# Sch.net
KiCad netlist of a schematic drawn in Altium Designer
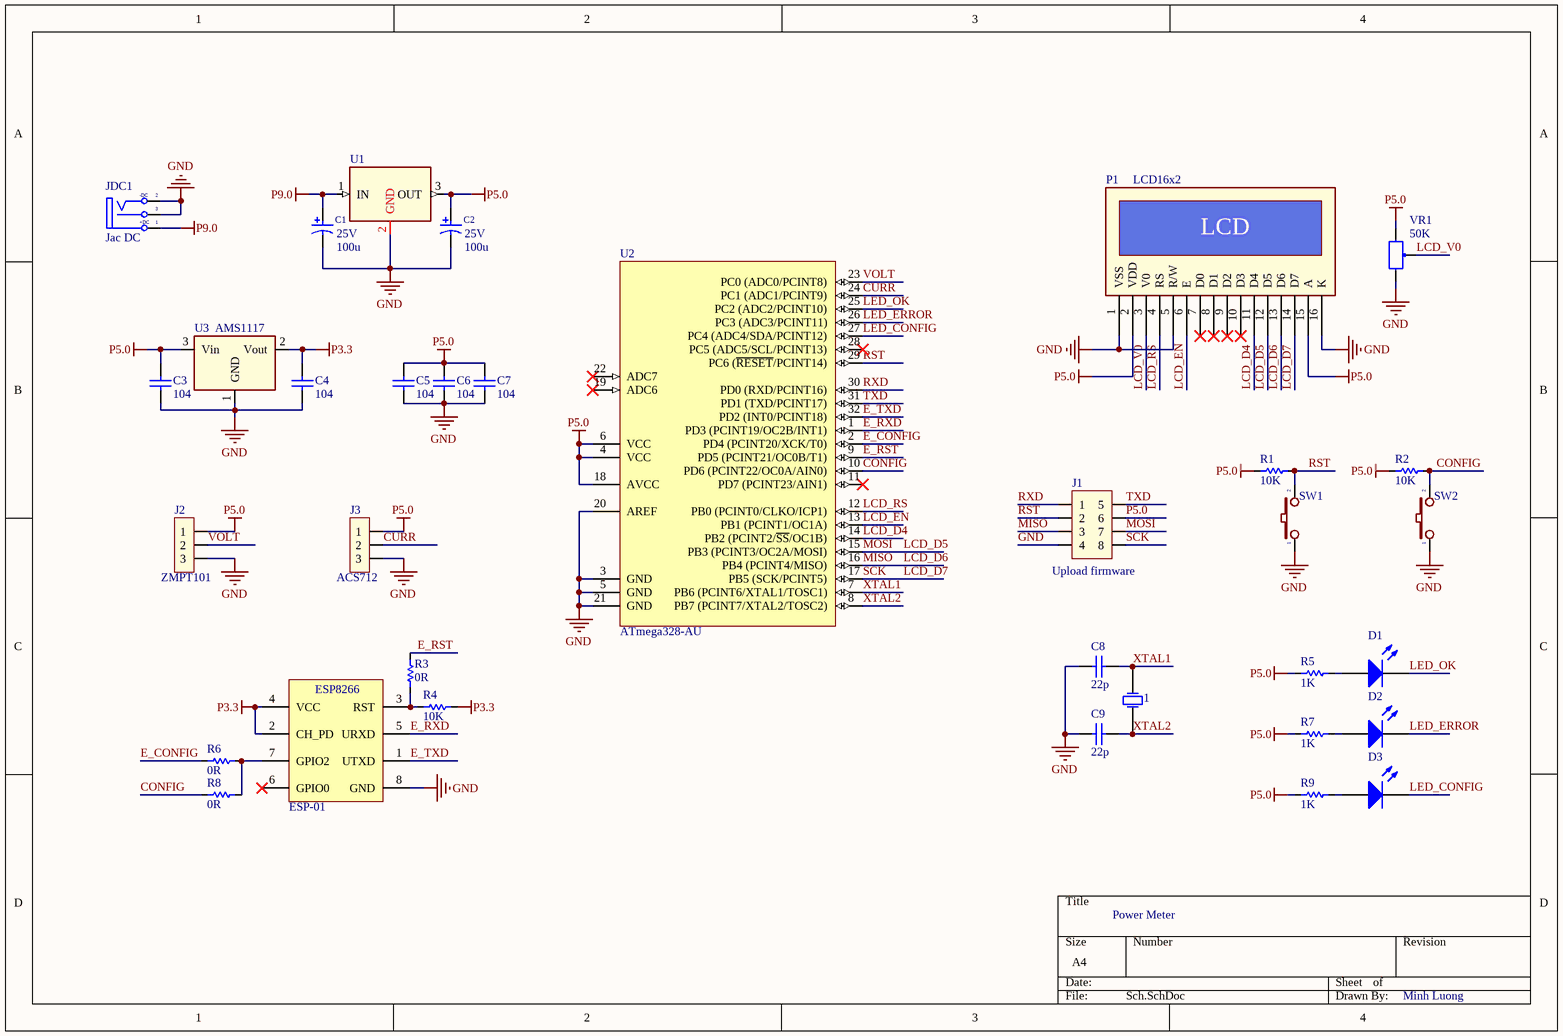
[diagram p0: Sch.SchDoc]

(export (version "E")
  (design (tool "Eeschema 10.0.6"))
  (components
    (comp (ref "1")
      (value "XTAL")
      (footprint "XTAL")
      (description "Crystal Oscillator")
      (fields (field (name "PUBLISHER") "Altium Limited"))
      (libsource (lib "jmctvs") (part "XTAL"))
    )
    (comp (ref "C1")
      (value "100u")
      (footprint "CAP_SMD_6_3MM")
      (description "Polarized Capacitor")
      (fields
        (field (name "MANUFACTURER") "FARNELL")
        (field (name "VOLT") "25V")
        (field (name "PUBLISHER") "Hoang Nguyen")
      )
      (libsource (lib "jmctvs") (part "Cap_Pol"))
    )
    (comp (ref "C2")
      (value "100u")
      (footprint "CAP_SMD_6_3MM")
      (description "Polarized Capacitor")
      (fields
        (field (name "MANUFACTURER") "FARNELL")
        (field (name "VOLT") "25V")
        (field (name "PUBLISHER") "Hoang Nguyen")
      )
      (libsource (lib "jmctvs") (part "Cap_Pol"))
    )
    (comp (ref "C3")
      (value "104")
      (footprint "CAP_SMD_0805")
      (description "Non-polarized Capacitor")
      (fields (field (name "Comment") "Cap Non-pol") (field (name "PUBLISHER") "Altium Limited"))
      (libsource (lib "jmctvs") (part "Cap Non-pol"))
    )
    (comp (ref "C4")
      (value "104")
      (footprint "CAP_SMD_0805")
      (description "Non-polarized Capacitor")
      (fields (field (name "Comment") "Cap Non-pol") (field (name "PUBLISHER") "Altium Limited"))
      (libsource (lib "jmctvs") (part "Cap Non-pol"))
    )
    (comp (ref "C5")
      (value "104")
      (footprint "CAP_SMD_0805")
      (description "Non-polarized Capacitor")
      (fields (field (name "Comment") "Cap Non-pol") (field (name "PUBLISHER") "Altium Limited"))
      (libsource (lib "jmctvs") (part "Cap Non-pol"))
    )
    (comp (ref "C6")
      (value "104")
      (footprint "CAP_SMD_0805")
      (description "Non-polarized Capacitor")
      (fields (field (name "Comment") "Cap Non-pol") (field (name "PUBLISHER") "Altium Limited"))
      (libsource (lib "jmctvs") (part "Cap Non-pol"))
    )
    (comp (ref "C7")
      (value "104")
      (footprint "CAP_SMD_0805")
      (description "Non-polarized Capacitor")
      (fields (field (name "Comment") "Cap Non-pol") (field (name "PUBLISHER") "Altium Limited"))
      (libsource (lib "jmctvs") (part "Cap Non-pol"))
    )
    (comp (ref "C8")
      (value "22p")
      (footprint "CAP_SMD_0805")
      (description "Non-polarized Capacitor")
      (fields (field (name "Comment") "Cap Non-pol") (field (name "PUBLISHER") "Altium Limited"))
      (libsource (lib "jmctvs") (part "Cap Non-pol"))
    )
    (comp (ref "C9")
      (value "22p")
      (footprint "CAP_SMD_0805")
      (description "Non-polarized Capacitor")
      (fields (field (name "Comment") "Cap Non-pol") (field (name "PUBLISHER") "Altium Limited"))
      (libsource (lib "jmctvs") (part "Cap Non-pol"))
    )
    (comp (ref "D1")
      (value "LED")
      (footprint "LED-0805 GREEN")
      (description "Typical LED")
      (fields (field (name "PUBLISHER") "Altium Limited"))
      (libsource (lib "jmctvs") (part "LED"))
    )
    (comp (ref "D2")
      (value "LED")
      (footprint "LED-0805 RED")
      (description "Typical LED")
      (fields (field (name "PUBLISHER") "Altium Limited"))
      (libsource (lib "jmctvs") (part "LED"))
    )
    (comp (ref "D3")
      (value "LED")
      (footprint "LED-0805 BLUE")
      (description "Typical LED")
      (fields (field (name "PUBLISHER") "Altium Limited"))
      (libsource (lib "jmctvs") (part "LED"))
    )
    (comp (ref "J1")
      (value "Upload firmware")
      (footprint "JP4x2")
      (description "Connector 4x2")
      (libsource (lib "jmctvs") (part "JP4x2"))
    )
    (comp (ref "J2")
      (value "ZMPT101")
      (footprint "JP3")
      (description "Jumper 3")
      (libsource (lib "jmctvs") (part "JP3"))
    )
    (comp (ref "J3")
      (value "ACS712")
      (footprint "JP3")
      (description "Jumper 3")
      (libsource (lib "jmctvs") (part "JP3"))
    )
    (comp (ref "JDC1")
      (value "Jac DC")
      (footprint "DC-IN")
      (description "Jac DC input")
      (libsource (lib "jmctvs") (part "DCIN"))
    )
    (comp (ref "P1") (value "LCD16x2") (footprint "LCD16x2") (libsource (lib "jmctvs") (part "LCD Text")))
    (comp (ref "R1")
      (value "10K")
      (footprint "RES_SMD_0805")
      (description "Resistor")
      (fields (field (name "Comment") "RESISTOR") (field (name "PUBLISHER") "Altium Limited"))
      (libsource (lib "jmctvs") (part "RESISTOR"))
    )
    (comp (ref "R2")
      (value "10K")
      (footprint "RES_SMD_0805")
      (description "Resistor")
      (fields (field (name "Comment") "RESISTOR") (field (name "PUBLISHER") "Altium Limited"))
      (libsource (lib "jmctvs") (part "RESISTOR"))
    )
    (comp (ref "R3")
      (value "0R")
      (footprint "RES_SMD_0805")
      (description "Resistor")
      (fields (field (name "Comment") "RESISTOR") (field (name "PUBLISHER") "Altium Limited"))
      (libsource (lib "jmctvs") (part "RESISTOR"))
    )
    (comp (ref "R4")
      (value "10K")
      (footprint "RES_SMD_0805")
      (description "Resistor")
      (fields (field (name "Comment") "RESISTOR") (field (name "PUBLISHER") "Altium Limited"))
      (libsource (lib "jmctvs") (part "RESISTOR"))
    )
    (comp (ref "R5")
      (value "1K")
      (footprint "RES_SMD_0805")
      (description "Resistor")
      (fields (field (name "Comment") "RESISTOR") (field (name "PUBLISHER") "Altium Limited"))
      (libsource (lib "jmctvs") (part "RESISTOR"))
    )
    (comp (ref "R6")
      (value "0R")
      (footprint "RES_SMD_0805")
      (description "Resistor")
      (fields (field (name "Comment") "RESISTOR") (field (name "PUBLISHER") "Altium Limited"))
      (libsource (lib "jmctvs") (part "RESISTOR"))
    )
    (comp (ref "R7")
      (value "1K")
      (footprint "RES_SMD_0805")
      (description "Resistor")
      (fields (field (name "Comment") "RESISTOR") (field (name "PUBLISHER") "Altium Limited"))
      (libsource (lib "jmctvs") (part "RESISTOR"))
    )
    (comp (ref "R8")
      (value "0R")
      (footprint "RES_SMD_0805")
      (description "Resistor")
      (fields (field (name "Comment") "RESISTOR") (field (name "PUBLISHER") "Altium Limited"))
      (libsource (lib "jmctvs") (part "RESISTOR"))
    )
    (comp (ref "R9")
      (value "1K")
      (footprint "RES_SMD_0805")
      (description "Resistor")
      (fields (field (name "Comment") "RESISTOR") (field (name "PUBLISHER") "Altium Limited"))
      (libsource (lib "jmctvs") (part "RESISTOR"))
    )
    (comp (ref "SW1")
      (value "SW")
      (footprint "SW2")
      (description "Switch button 2 pin")
      (libsource (lib "jmctvs") (part "SW2"))
    )
    (comp (ref "SW2")
      (value "SW")
      (footprint "SW2")
      (description "Switch button 2 pin")
      (libsource (lib "jmctvs") (part "SW2"))
    )
    (comp (ref "U1")
      (value "LM78xx")
      (footprint "TO-263")
      (description "Regulator")
      (fields
        (field (name "MANUFACTURER") "Fairchild Semiconductor Corporation")
        (field (name "TOLERANCE") "4 %")
        (field (name "PUBLISHER") "Hoang Nguyen")
      )
      (libsource (lib "jmctvs") (part "LM78xx"))
    )
    (comp (ref "U2")
      (value "ATmega328-AU")
      (footprint "TQFP32A")
      (libsource (lib "jmctvs") (part "ATmega328-AU"))
    )
    (comp (ref "U3")
      (value "AMS1117")
      (footprint "SOT223")
      (description "Regulator SMD Chip")
      (fields (field (name "DESIGNED BY") "John MacTavish"))
      (libsource (lib "jmctvs") (part "AMS1117"))
    )
    (comp (ref "U4")
      (value "ESP-01")
      (footprint "jmctvs:ESP8266")
      (description "ESP-12 Wi-Fi Module")
      (libsource (lib "jmctvs") (part "ESP8266-01"))
    )
    (comp (ref "VR1")
      (value "50K")
      (footprint "VR")
      (description "Var Resistor")
      (libsource (lib "jmctvs") (part "VR"))
    )
  )
  (nets
    (net (code "1") (name "/CONFIG") (class "Default")
      (node (ref "R2") (pin "1") (pinfunction "1_1") (pintype "passive"))
      (node (ref "R8") (pin "1") (pinfunction "1_1") (pintype "passive"))
      (node (ref "SW2") (pin "2") (pinfunction "2_2") (pintype "passive"))
      (node (ref "U2") (pin "10") (pinfunction "PD6_(PCINT22/OC0A/AIN0)_10") (pintype "bidirectional"))
    )
    (net (code "2") (name "/CURR") (class "Default")
      (node (ref "J3") (pin "2") (pinfunction "2_2") (pintype "passive"))
      (node (ref "U2") (pin "24") (pinfunction "PC1_(ADC1/PCINT9)_24") (pintype "bidirectional"))
    )
    (net (code "3") (name "/E_CONFIG") (class "Default")
      (node (ref "R6") (pin "1") (pinfunction "1_1") (pintype "passive"))
      (node (ref "U2") (pin "2") (pinfunction "PD4_(PCINT20/XCK/T0)_2") (pintype "bidirectional"))
    )
    (net (code "4") (name "/E_RST") (class "Default")
      (node (ref "R3") (pin "1") (pinfunction "1_1") (pintype "passive"))
      (node (ref "U2") (pin "9") (pinfunction "PD5_(PCINT21/OC0B/T1)_9") (pintype "bidirectional"))
    )
    (net (code "5") (name "/E_RXD") (class "Default")
      (node (ref "U2") (pin "1") (pinfunction "PD3_(PCINT19/OC2B/INT1)_1") (pintype "bidirectional"))
      (node (ref "U4") (pin "5") (pinfunction "URXD_5") (pintype "passive"))
    )
    (net (code "6") (name "/E_TXD") (class "Default")
      (node (ref "U2") (pin "32") (pinfunction "PD2_(INT0/PCINT18)_32") (pintype "bidirectional"))
      (node (ref "U4") (pin "1") (pinfunction "UTXD_1") (pintype "passive"))
    )
    (net (code "7") (name "/LCD_D4") (class "Default")
      (node (ref "P1") (pin "11") (pinfunction "D4_11") (pintype "passive"))
      (node (ref "U2") (pin "14") (pinfunction "PB2_(PCINT2/~{SS}/OC1B)_14") (pintype "bidirectional"))
    )
    (net (code "8") (name "/LCD_D5") (class "Default")
      (node (ref "J1") (pin "7") (pinfunction "7_7") (pintype "passive"))
      (node (ref "P1") (pin "12") (pinfunction "D5_12") (pintype "passive"))
      (node (ref "U2") (pin "15") (pinfunction "PB3_(PCINT3/OC2A/MOSI)_15") (pintype "bidirectional"))
    )
    (net (code "9") (name "/LCD_D6") (class "Default")
      (node (ref "J1") (pin "3") (pinfunction "3_3") (pintype "passive"))
      (node (ref "P1") (pin "13") (pinfunction "D6_13") (pintype "passive"))
      (node (ref "U2") (pin "16") (pinfunction "PB4_(PCINT4/MISO)_16") (pintype "bidirectional"))
    )
    (net (code "10") (name "/LCD_D7") (class "Default")
      (node (ref "J1") (pin "8") (pinfunction "8_8") (pintype "passive"))
      (node (ref "P1") (pin "14") (pinfunction "D7_14") (pintype "passive"))
      (node (ref "U2") (pin "17") (pinfunction "PB5_(SCK/PCINT5)_17") (pintype "bidirectional"))
    )
    (net (code "11") (name "/LCD_EN") (class "Default")
      (node (ref "P1") (pin "6") (pinfunction "E_6") (pintype "passive"))
      (node (ref "U2") (pin "13") (pinfunction "PB1_(PCINT1/OC1A)_13") (pintype "bidirectional"))
    )
    (net (code "12") (name "/LCD_RS") (class "Default")
      (node (ref "P1") (pin "4") (pinfunction "RS_4") (pintype "passive"))
      (node (ref "U2") (pin "12") (pinfunction "PB0_(PCINT0/CLKO/ICP1)_12") (pintype "bidirectional"))
    )
    (net (code "13") (name "/LCD_V0") (class "Default")
      (node (ref "P1") (pin "3") (pinfunction "V0_3") (pintype "passive"))
      (node (ref "VR1") (pin "2") (pinfunction "2_2") (pintype "passive"))
    )
    (net (code "14") (name "/LED_CONFIG") (class "Default")
      (node (ref "D3") (pin "2") (pinfunction "K_2") (pintype "passive"))
      (node (ref "U2") (pin "27") (pinfunction "PC4_(ADC4/SDA/PCINT12)_27") (pintype "bidirectional"))
    )
    (net (code "15") (name "/LED_ERROR") (class "Default")
      (node (ref "D2") (pin "2") (pinfunction "K_2") (pintype "passive"))
      (node (ref "U2") (pin "26") (pinfunction "PC3_(ADC3/PCINT11)_26") (pintype "bidirectional"))
    )
    (net (code "16") (name "/LED_OK") (class "Default")
      (node (ref "D1") (pin "2") (pinfunction "K_2") (pintype "passive"))
      (node (ref "U2") (pin "25") (pinfunction "PC2_(ADC2/PCINT10)_25") (pintype "bidirectional"))
    )
    (net (code "17") (name "/RST") (class "Default")
      (node (ref "J1") (pin "2") (pinfunction "2_2") (pintype "passive"))
      (node (ref "R1") (pin "1") (pinfunction "1_1") (pintype "passive"))
      (node (ref "SW1") (pin "2") (pinfunction "2_2") (pintype "passive"))
      (node (ref "U2") (pin "29") (pinfunction "PC6_(~{RESET}/PCINT14)_29") (pintype "bidirectional"))
    )
    (net (code "18") (name "/RXD") (class "Default")
      (node (ref "J1") (pin "1") (pinfunction "1_1") (pintype "passive"))
      (node (ref "U2") (pin "30") (pinfunction "PD0_(RXD/PCINT16)_30") (pintype "bidirectional"))
    )
    (net (code "19") (name "/TXD") (class "Default")
      (node (ref "J1") (pin "5") (pinfunction "5_5") (pintype "passive"))
      (node (ref "U2") (pin "31") (pinfunction "PD1_(TXD/PCINT17)_31") (pintype "bidirectional"))
    )
    (net (code "20") (name "/VOLT") (class "Default")
      (node (ref "J2") (pin "2") (pinfunction "2_2") (pintype "passive"))
      (node (ref "U2") (pin "23") (pinfunction "PC0_(ADC0/PCINT8)_23") (pintype "bidirectional"))
    )
    (net (code "21") (name "/XTAL1") (class "Default")
      (node (ref "1") (pin "2") (pinfunction "OSC2_2") (pintype "passive"))
      (node (ref "C8") (pin "2") (pinfunction "2_2") (pintype "passive"))
      (node (ref "U2") (pin "7") (pinfunction "PB6_(PCINT6/XTAL1/TOSC1)_7") (pintype "bidirectional"))
    )
    (net (code "22") (name "/XTAL2") (class "Default")
      (node (ref "1") (pin "1") (pinfunction "OSC1_1") (pintype "passive"))
      (node (ref "C9") (pin "2") (pinfunction "2_2") (pintype "passive"))
      (node (ref "U2") (pin "8") (pinfunction "PB7_(PCINT7/XTAL2/TOSC2)_8") (pintype "bidirectional"))
    )
    (net (code "23") (name "GND") (class "Default")
      (node (ref "C1") (pin "2") (pinfunction "2_2") (pintype "passive"))
      (node (ref "C2") (pin "2") (pinfunction "2_2") (pintype "passive"))
      (node (ref "C3") (pin "1") (pinfunction "1_1") (pintype "passive"))
      (node (ref "C4") (pin "1") (pinfunction "1_1") (pintype "passive"))
      (node (ref "C5") (pin "1") (pinfunction "1_1") (pintype "passive"))
      (node (ref "C6") (pin "1") (pinfunction "1_1") (pintype "passive"))
      (node (ref "C7") (pin "1") (pinfunction "1_1") (pintype "passive"))
      (node (ref "C8") (pin "1") (pinfunction "1_1") (pintype "passive"))
      (node (ref "C9") (pin "1") (pinfunction "1_1") (pintype "passive"))
      (node (ref "J1") (pin "4") (pinfunction "4_4") (pintype "passive"))
      (node (ref "J2") (pin "3") (pinfunction "3_3") (pintype "passive"))
      (node (ref "J3") (pin "3") (pinfunction "3_3") (pintype "passive"))
      (node (ref "JDC1") (pin "2") (pinfunction "TN_2") (pintype "passive"))
      (node (ref "JDC1") (pin "3") (pinfunction "S_3") (pintype "power_in"))
      (node (ref "P1") (pin "1") (pinfunction "VSS_1") (pintype "passive"))
      (node (ref "P1") (pin "16") (pinfunction "K_16") (pintype "passive"))
      (node (ref "P1") (pin "5") (pinfunction "R/W_5") (pintype "passive"))
      (node (ref "SW1") (pin "1") (pinfunction "1_1") (pintype "passive"))
      (node (ref "SW2") (pin "1") (pinfunction "1_1") (pintype "passive"))
      (node (ref "U1") (pin "2") (pinfunction "GND_2") (pintype "power_in"))
      (node (ref "U2") (pin "20") (pinfunction "AREF_20") (pintype "passive"))
      (node (ref "U2") (pin "21") (pinfunction "GND_21") (pintype "power_in"))
      (node (ref "U2") (pin "3") (pinfunction "GND_3") (pintype "power_in"))
      (node (ref "U2") (pin "5") (pinfunction "GND_5") (pintype "power_in"))
      (node (ref "U3") (pin "1") (pinfunction "GND_1") (pintype "passive"))
      (node (ref "U4") (pin "8") (pinfunction "GND_8") (pintype "passive"))
      (node (ref "VR1") (pin "3") (pinfunction "3_3") (pintype "passive"))
    )
    (net (code "24") (name "Net-(D1-A)") (class "Default")
      (node (ref "D1") (pin "1") (pinfunction "A_1") (pintype "passive"))
      (node (ref "R5") (pin "1") (pinfunction "1_1") (pintype "passive"))
    )
    (net (code "25") (name "Net-(D2-A)") (class "Default")
      (node (ref "D2") (pin "1") (pinfunction "A_1") (pintype "passive"))
      (node (ref "R7") (pin "1") (pinfunction "1_1") (pintype "passive"))
    )
    (net (code "26") (name "Net-(D3-A)") (class "Default")
      (node (ref "D3") (pin "1") (pinfunction "A_1") (pintype "passive"))
      (node (ref "R9") (pin "1") (pinfunction "1_1") (pintype "passive"))
    )
    (net (code "27") (name "Net-(U4-GPIO2)") (class "Default")
      (node (ref "R6") (pin "2") (pinfunction "2_2") (pintype "passive"))
      (node (ref "R8") (pin "2") (pinfunction "2_2") (pintype "passive"))
      (node (ref "U4") (pin "7") (pinfunction "GPIO2_7") (pintype "passive"))
    )
    (net (code "28") (name "Net-(U4-RST)") (class "Default")
      (node (ref "R3") (pin "2") (pinfunction "2_2") (pintype "passive"))
      (node (ref "R4") (pin "2") (pinfunction "2_2") (pintype "passive"))
      (node (ref "U4") (pin "3") (pinfunction "RST_3") (pintype "passive"))
    )
    (net (code "29") (name "P3.3") (class "Default")
      (node (ref "C4") (pin "2") (pinfunction "2_2") (pintype "passive"))
      (node (ref "R4") (pin "1") (pinfunction "1_1") (pintype "passive"))
      (node (ref "U3") (pin "2") (pinfunction "Vout_2") (pintype "passive"))
      (node (ref "U4") (pin "2") (pinfunction "CH_PD_2") (pintype "passive"))
      (node (ref "U4") (pin "4") (pinfunction "VCC_4") (pintype "passive"))
    )
    (net (code "30") (name "P5.0") (class "Default")
      (node (ref "C2") (pin "1") (pinfunction "1_1") (pintype "passive"))
      (node (ref "C3") (pin "2") (pinfunction "2_2") (pintype "passive"))
      (node (ref "C5") (pin "2") (pinfunction "2_2") (pintype "passive"))
      (node (ref "C6") (pin "2") (pinfunction "2_2") (pintype "passive"))
      (node (ref "C7") (pin "2") (pinfunction "2_2") (pintype "passive"))
      (node (ref "J1") (pin "6") (pinfunction "6_6") (pintype "passive"))
      (node (ref "J2") (pin "1") (pinfunction "1_1") (pintype "passive"))
      (node (ref "J3") (pin "1") (pinfunction "1_1") (pintype "passive"))
      (node (ref "P1") (pin "15") (pinfunction "A_15") (pintype "passive"))
      (node (ref "P1") (pin "2") (pinfunction "VDD_2") (pintype "passive"))
      (node (ref "R1") (pin "2") (pinfunction "2_2") (pintype "passive"))
      (node (ref "R2") (pin "2") (pinfunction "2_2") (pintype "passive"))
      (node (ref "R5") (pin "2") (pinfunction "2_2") (pintype "passive"))
      (node (ref "R7") (pin "2") (pinfunction "2_2") (pintype "passive"))
      (node (ref "R9") (pin "2") (pinfunction "2_2") (pintype "passive"))
      (node (ref "U1") (pin "3") (pinfunction "OUT_3") (pintype "output"))
      (node (ref "U2") (pin "18") (pinfunction "AVCC_18") (pintype "power_in"))
      (node (ref "U2") (pin "4") (pinfunction "VCC_4") (pintype "power_in"))
      (node (ref "U2") (pin "6") (pinfunction "VCC_6") (pintype "power_in"))
      (node (ref "U3") (pin "3") (pinfunction "Vin_3") (pintype "passive"))
      (node (ref "VR1") (pin "1") (pinfunction "1_1") (pintype "passive"))
    )
    (net (code "31") (name "P9.0") (class "Default")
      (node (ref "C1") (pin "1") (pinfunction "1_1") (pintype "passive"))
      (node (ref "JDC1") (pin "1") (pinfunction "T_1") (pintype "passive"))
      (node (ref "U1") (pin "1") (pinfunction "IN_1") (pintype "input"))
    )
    (net (code "32") (name "unconnected-(P1-D0-Pad7)") (class "Default")
      (node (ref "P1") (pin "7") (pinfunction "D0_7") (pintype "passive+no_connect"))
    )
    (net (code "33") (name "unconnected-(P1-D1-Pad8)") (class "Default")
      (node (ref "P1") (pin "8") (pinfunction "D1_8") (pintype "passive+no_connect"))
    )
    (net (code "34") (name "unconnected-(P1-D2-Pad9)") (class "Default")
      (node (ref "P1") (pin "9") (pinfunction "D2_9") (pintype "passive+no_connect"))
    )
    (net (code "35") (name "unconnected-(P1-D3-Pad10)") (class "Default")
      (node (ref "P1") (pin "10") (pinfunction "D3_10") (pintype "passive+no_connect"))
    )
    (net (code "36") (name "unconnected-(U2-ADC6-Pad19)") (class "Default")
      (node (ref "U2") (pin "19") (pinfunction "ADC6_19") (pintype "input+no_connect"))
    )
    (net (code "37") (name "unconnected-(U2-ADC7-Pad22)") (class "Default")
      (node (ref "U2") (pin "22") (pinfunction "ADC7_22") (pintype "input+no_connect"))
    )
    (net (code "38") (name "unconnected-(U2-PC5_(ADC5{slash}SCL{slash}PCINT13)-Pad28)") (class "Default")
      (node (ref "U2") (pin "28") (pinfunction "PC5_(ADC5/SCL/PCINT13)_28") (pintype "bidirectional+no_connect"))
    )
    (net (code "39") (name "unconnected-(U2-PD7_(PCINT23{slash}AIN1)-Pad11)") (class "Default")
      (node (ref "U2") (pin "11") (pinfunction "PD7_(PCINT23/AIN1)_11") (pintype "bidirectional+no_connect"))
    )
    (net (code "40") (name "unconnected-(U4-GPIO0-Pad6)") (class "Default")
      (node (ref "U4") (pin "6") (pinfunction "GPIO0_6") (pintype "passive+no_connect"))
    )
  )
)
